# Stackduino-SMD.net
KiCad netlist of a schematic drawn in EAGLE
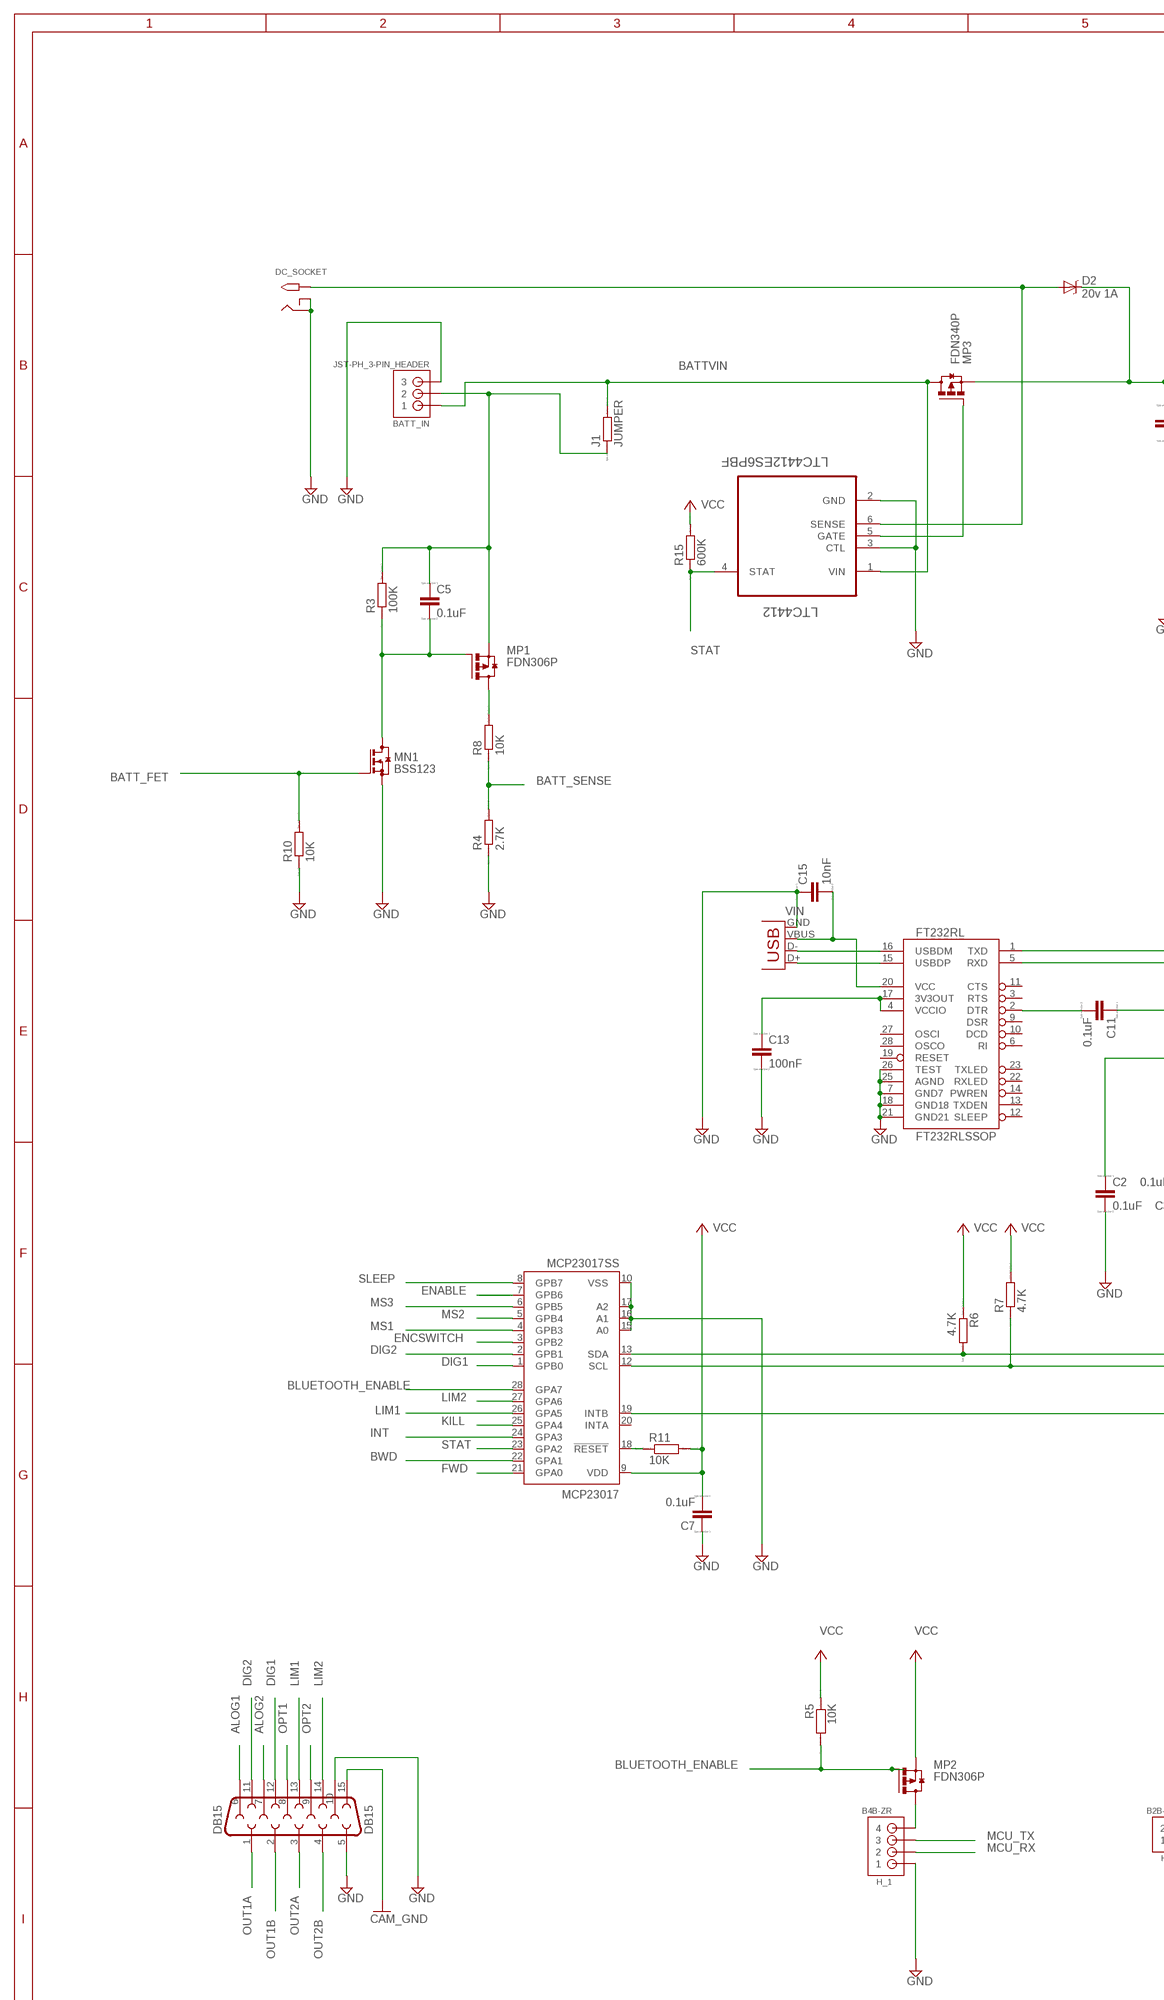
[diagram p0: schematic, sheet 1, part 1 of 2]
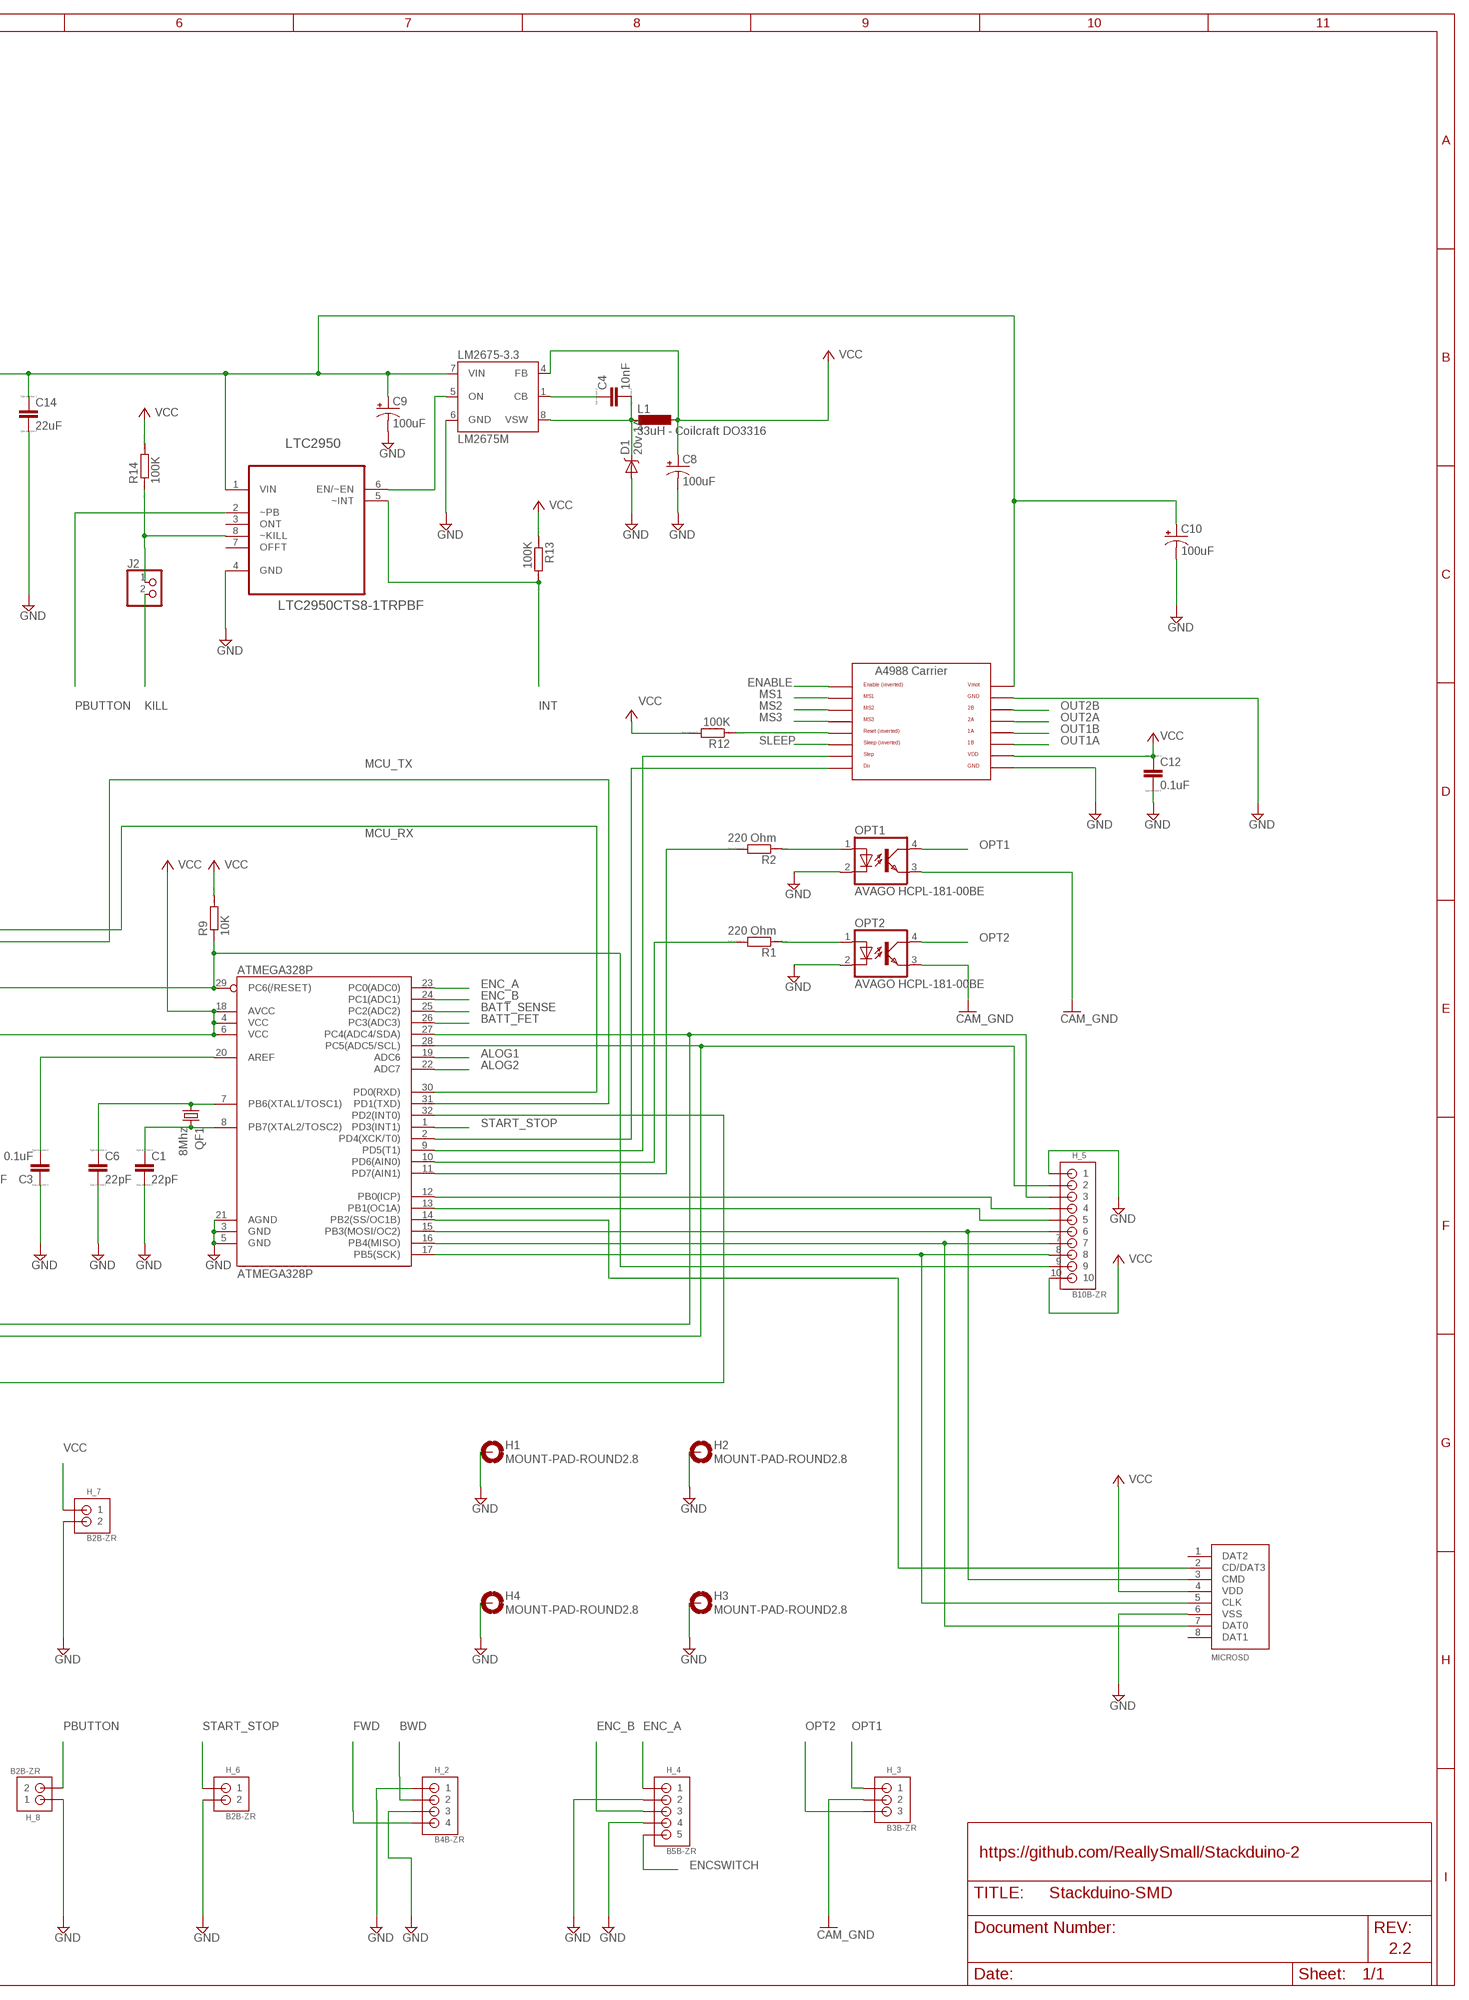
[diagram p1: schematic, sheet 1, part 2 of 2]

(export (version "E")
  (design (tool "Eeschema 10.0.6"))
  (components
    (comp (ref "A4988_CARRIER")
      (value "A4988BREAKOUT")
      (footprint "eagle-import:A4988BREAKOUT")
      (libsource (lib "eagle-import") (part "A4988BREAKOUT"))
    )
    (comp (ref "ATMEGA328P")
      (value "ATMEGA328P")
      (footprint "eagle-import:TQFP32-08")
      (libsource (lib "eagle-import") (part "ATMEGA328_SMT"))
    )
    (comp (ref "BATT_IN")
      (value "JST-PH_3-PIN_HEADER")
      (footprint "eagle-import:JST_B3B-PH_HEADER")
      (libsource (lib "eagle-import") (part "JST-PH_3-PIN_HEADER"))
    )
    (comp (ref "C1")
      (value "22pF")
      (footprint "eagle-import:C0805")
      (libsource (lib "eagle-import") (part "C"))
    )
    (comp (ref "C2")
      (value "0.1uF")
      (footprint "eagle-import:C0805")
      (libsource (lib "eagle-import") (part "C"))
    )
    (comp (ref "C3")
      (value "0.1uF")
      (footprint "eagle-import:C0805")
      (libsource (lib "eagle-import") (part "C"))
    )
    (comp (ref "C4")
      (value "10nF")
      (footprint "eagle-import:C0805")
      (libsource (lib "eagle-import") (part "C"))
    )
    (comp (ref "C5")
      (value "0.1uF")
      (footprint "eagle-import:C0805")
      (libsource (lib "eagle-import") (part "C"))
    )
    (comp (ref "C6")
      (value "22pF")
      (footprint "eagle-import:C0805")
      (libsource (lib "eagle-import") (part "C"))
    )
    (comp (ref "C7")
      (value "0.1uF")
      (footprint "eagle-import:C0805")
      (libsource (lib "eagle-import") (part "C"))
    )
    (comp (ref "C8")
      (value "100uF")
      (footprint "eagle-import:PANASONIC_D")
      (libsource (lib "eagle-import") (part "CAP_POLD"))
    )
    (comp (ref "C9")
      (value "100uF")
      (footprint "eagle-import:PANASONIC_D")
      (libsource (lib "eagle-import") (part "CAP_POLD"))
    )
    (comp (ref "C10")
      (value "100uF")
      (footprint "eagle-import:PANASONIC_D")
      (libsource (lib "eagle-import") (part "CAP_POLD"))
    )
    (comp (ref "C11")
      (value "0.1uF")
      (footprint "eagle-import:C0805")
      (libsource (lib "eagle-import") (part "C"))
    )
    (comp (ref "C12")
      (value "0.1uF")
      (footprint "eagle-import:C0805")
      (libsource (lib "eagle-import") (part "C"))
    )
    (comp (ref "C13")
      (value "100nF")
      (footprint "eagle-import:C0805")
      (libsource (lib "eagle-import") (part "C"))
    )
    (comp (ref "C14")
      (value "22uF")
      (footprint "eagle-import:C0805")
      (libsource (lib "eagle-import") (part "C"))
    )
    (comp (ref "C15")
      (value "10nF")
      (footprint "eagle-import:C0805")
      (libsource (lib "eagle-import") (part "C"))
    )
    (comp (ref "D1")
      (value "20v 1A")
      (footprint "eagle-import:SMA-DIODE")
      (libsource (lib "eagle-import") (part "MBRA140"))
    )
    (comp (ref "D2")
      (value "20v 1A")
      (footprint "eagle-import:SMA-DIODE")
      (libsource (lib "eagle-import") (part "MBRA140"))
    )
    (comp (ref "DB15")
      (value "DB15")
      (footprint "eagle-import:DB15")
      (libsource (lib "eagle-import") (part "DB15"))
    )
    (comp (ref "DC_SOCKET")
      (value "2.1MMJACKTHM")
      (footprint "eagle-import:PJ-102A")
      (libsource (lib "eagle-import") (part "2.1MMJACKTHM"))
    )
    (comp (ref "FT232RL")
      (value "FT232RLSSOP")
      (footprint "eagle-import:SSOP28DB")
      (libsource (lib "eagle-import") (part "FT232RLSSOP"))
    )
    (comp (ref "H1")
      (value "MOUNT-PAD-ROUND2.8")
      (footprint "eagle-import:2,8-PAD")
      (libsource (lib "eagle-import") (part "MOUNT-PAD-ROUND2.8"))
    )
    (comp (ref "H2")
      (value "MOUNT-PAD-ROUND2.8")
      (footprint "eagle-import:2,8-PAD")
      (libsource (lib "eagle-import") (part "MOUNT-PAD-ROUND2.8"))
    )
    (comp (ref "H3")
      (value "MOUNT-PAD-ROUND2.8")
      (footprint "eagle-import:2,8-PAD")
      (libsource (lib "eagle-import") (part "MOUNT-PAD-ROUND2.8"))
    )
    (comp (ref "H4")
      (value "MOUNT-PAD-ROUND2.8")
      (footprint "eagle-import:2,8-PAD")
      (libsource (lib "eagle-import") (part "MOUNT-PAD-ROUND2.8"))
    )
    (comp (ref "H_1")
      (value "B4B-ZR")
      (footprint "eagle-import:B4B-ZR")
      (libsource (lib "eagle-import") (part "B4B-ZR"))
    )
    (comp (ref "H_2")
      (value "B4B-ZR")
      (footprint "eagle-import:B4B-ZR")
      (libsource (lib "eagle-import") (part "B4B-ZR"))
    )
    (comp (ref "H_3")
      (value "B3B-ZR")
      (footprint "eagle-import:B3B-ZR")
      (libsource (lib "eagle-import") (part "B3B-ZR"))
    )
    (comp (ref "H_4")
      (value "B5B-ZR")
      (footprint "eagle-import:B5B-ZR")
      (libsource (lib "eagle-import") (part "B5B-ZR"))
    )
    (comp (ref "H_5")
      (value "B10B-ZR")
      (footprint "eagle-import:B10B-ZR")
      (libsource (lib "eagle-import") (part "B10B-ZR"))
    )
    (comp (ref "H_6")
      (value "B2B-ZR")
      (footprint "eagle-import:B2B-ZR")
      (libsource (lib "eagle-import") (part "B2B-ZR"))
    )
    (comp (ref "H_7")
      (value "B2B-ZR")
      (footprint "eagle-import:B2B-ZR")
      (libsource (lib "eagle-import") (part "B2B-ZR"))
    )
    (comp (ref "H_8")
      (value "B2B-ZR")
      (footprint "eagle-import:B2B-ZR")
      (libsource (lib "eagle-import") (part "B2B-ZR"))
    )
    (comp (ref "J1")
      (value "JUMPER")
      (footprint "eagle-import:R0805")
      (libsource (lib "eagle-import") (part "R"))
    )
    (comp (ref "J2")
      (value "PINHD-1X2")
      (footprint "eagle-import:1X02")
      (libsource (lib "eagle-import") (part "PINHD-1X2"))
    )
    (comp (ref "L1")
      (value "33uH - Coilcraft DO3316")
      (footprint "eagle-import:DO3316P")
      (libsource (lib "eagle-import") (part "DO3316P"))
    )
    (comp (ref "LM2675-3.3")
      (value "LM2675M")
      (footprint "eagle-import:SO08")
      (libsource (lib "eagle-import") (part "LM2675M"))
    )
    (comp (ref "LTC2950")
      (value "LTC2950CTS8-1TRPBF")
      (footprint "eagle-import:SOT65P280X100-8N")
      (fields (field (name "MPN") "LTC2950CTS8-1#TRPBF"))
      (libsource (lib "eagle-import") (part "LTC2950CTS8-1TRPBF"))
    )
    (comp (ref "LTC4412")
      (value "LTC4412ES6PBF")
      (footprint "eagle-import:SOT95P280X100-6N")
      (fields (field (name "MPN") "LTC4412ES6#PBF"))
      (libsource (lib "eagle-import") (part "LTC4412ES6PBF"))
    )
    (comp (ref "MCP23017")
      (value "MCP23017SS")
      (footprint "eagle-import:SSOP28")
      (libsource (lib "eagle-import") (part "MCP23017SS"))
    )
    (comp (ref "MICROSD")
      (value "CON_MICROSDHINGED")
      (footprint "eagle-import:CON_MICROSD_HINGED")
      (libsource (lib "eagle-import") (part "CON_MICROSDHINGED"))
    )
    (comp (ref "MN1")
      (value "BSS123")
      (footprint "eagle-import:SOT23")
      (libsource (lib "eagle-import") (part "BSS123"))
    )
    (comp (ref "MP1")
      (value "FDN306P")
      (footprint "eagle-import:SUPER-SOT3")
      (libsource (lib "eagle-import") (part "FDN360P"))
    )
    (comp (ref "MP2")
      (value "FDN306P")
      (footprint "eagle-import:SUPER-SOT3")
      (libsource (lib "eagle-import") (part "FDN360P"))
    )
    (comp (ref "MP3")
      (value "FDN340P")
      (footprint "eagle-import:SUPER-SOT3")
      (libsource (lib "eagle-import") (part "FDN360P"))
    )
    (comp (ref "OPT1")
      (value "AVAGO HCPL-181-00BE")
      (footprint "eagle-import:SMD4")
      (libsource (lib "eagle-import") (part "LTV816S"))
    )
    (comp (ref "OPT2")
      (value "AVAGO HCPL-181-00BE")
      (footprint "eagle-import:SMD4")
      (libsource (lib "eagle-import") (part "LTV816S"))
    )
    (comp (ref "QF1")
      (value "8Mhz")
      (footprint "eagle-import:HC49U-V")
      (libsource (lib "eagle-import") (part "CRYSTALHC49U-V"))
    )
    (comp (ref "R1")
      (value "220 Ohm")
      (footprint "eagle-import:R0805")
      (libsource (lib "eagle-import") (part "R"))
    )
    (comp (ref "R2")
      (value "220 Ohm")
      (footprint "eagle-import:R0805")
      (libsource (lib "eagle-import") (part "R"))
    )
    (comp (ref "R3")
      (value "100K")
      (footprint "eagle-import:R0805")
      (libsource (lib "eagle-import") (part "R"))
    )
    (comp (ref "R4")
      (value "2.7K")
      (footprint "eagle-import:R0805")
      (libsource (lib "eagle-import") (part "R"))
    )
    (comp (ref "R5")
      (value "10K")
      (footprint "eagle-import:R0805")
      (libsource (lib "eagle-import") (part "R"))
    )
    (comp (ref "R6")
      (value "4.7K")
      (footprint "eagle-import:R0805")
      (libsource (lib "eagle-import") (part "R"))
    )
    (comp (ref "R7")
      (value "4.7K")
      (footprint "eagle-import:R0805")
      (libsource (lib "eagle-import") (part "R"))
    )
    (comp (ref "R8")
      (value "10K")
      (footprint "eagle-import:R0805")
      (libsource (lib "eagle-import") (part "R"))
    )
    (comp (ref "R9")
      (value "10K")
      (footprint "eagle-import:R0805")
      (libsource (lib "eagle-import") (part "R"))
    )
    (comp (ref "R10")
      (value "10K")
      (footprint "eagle-import:R0805")
      (libsource (lib "eagle-import") (part "R"))
    )
    (comp (ref "R11")
      (value "10K")
      (footprint "eagle-import:R0805")
      (libsource (lib "eagle-import") (part "R"))
    )
    (comp (ref "R12")
      (value "100K")
      (footprint "eagle-import:R0805")
      (libsource (lib "eagle-import") (part "R"))
    )
    (comp (ref "R13")
      (value "100K")
      (footprint "eagle-import:R0805")
      (libsource (lib "eagle-import") (part "R"))
    )
    (comp (ref "R14")
      (value "100K")
      (footprint "eagle-import:R0805")
      (libsource (lib "eagle-import") (part "R"))
    )
    (comp (ref "R15")
      (value "600K")
      (footprint "eagle-import:R0805")
      (libsource (lib "eagle-import") (part "R"))
    )
    (comp (ref "USB")
      (value "USBSMD")
      (footprint "eagle-import:USB-MINIB")
      (libsource (lib "eagle-import") (part "USBSMD"))
    )
  )
  (nets
    (net (code "1") (name "/ALOG1") (class "Default")
      (node (ref "ATMEGA328P") (pin "19") (pinfunction "ADC6_19") (pintype "bidirectional"))
      (node (ref "DB15") (pin "6") (pinfunction "6_6") (pintype "passive"))
    )
    (net (code "2") (name "/ALOG2") (class "Default")
      (node (ref "ATMEGA328P") (pin "22") (pinfunction "ADC7_22") (pintype "bidirectional"))
      (node (ref "DB15") (pin "7") (pinfunction "7_7") (pintype "passive"))
    )
    (net (code "3") (name "/BATTVIN") (class "Default")
      (node (ref "BATT_IN") (pin "P1") (pinfunction "1_P1") (pintype "bidirectional"))
      (node (ref "J1") (pin "2") (pinfunction "2_2") (pintype "passive"))
      (node (ref "LTC4412") (pin "1") (pinfunction "VIN_1") (pintype "power_in"))
      (node (ref "MP3") (pin "3") (pinfunction "D_3") (pintype "passive"))
    )
    (net (code "4") (name "/BATT_FET") (class "Default")
      (node (ref "ATMEGA328P") (pin "26") (pinfunction "PC3(ADC3)_26") (pintype "bidirectional"))
      (node (ref "MN1") (pin "1") (pinfunction "G_1") (pintype "passive"))
      (node (ref "R10") (pin "2") (pinfunction "2_2") (pintype "passive"))
    )
    (net (code "5") (name "/BATT_SENSE") (class "Default")
      (node (ref "ATMEGA328P") (pin "25") (pinfunction "PC2(ADC2)_25") (pintype "bidirectional"))
      (node (ref "R4") (pin "2") (pinfunction "2_2") (pintype "passive"))
      (node (ref "R8") (pin "1") (pinfunction "1_1") (pintype "passive"))
    )
    (net (code "6") (name "/BLUETOOTH_ENABLE") (class "Default")
      (node (ref "MCP23017") (pin "28") (pinfunction "GPA7_28") (pintype "bidirectional"))
      (node (ref "MP2") (pin "1") (pinfunction "G_1") (pintype "passive"))
      (node (ref "R5") (pin "2") (pinfunction "2_2") (pintype "passive"))
    )
    (net (code "7") (name "/BWD") (class "Default")
      (node (ref "H_2") (pin "2") (pinfunction "2_2") (pintype "bidirectional"))
      (node (ref "MCP23017") (pin "22") (pinfunction "GPA1_22") (pintype "bidirectional"))
    )
    (net (code "8") (name "/DIG1") (class "Default")
      (node (ref "DB15") (pin "12") (pinfunction "12_12") (pintype "passive"))
      (node (ref "MCP23017") (pin "1") (pinfunction "GPB0_1") (pintype "bidirectional"))
    )
    (net (code "9") (name "/DIG2") (class "Default")
      (node (ref "DB15") (pin "11") (pinfunction "11_11") (pintype "passive"))
      (node (ref "MCP23017") (pin "2") (pinfunction "GPB1_2") (pintype "bidirectional"))
    )
    (net (code "10") (name "/ENABLE") (class "Default")
      (node (ref "A4988_CARRIER") (pin "EN") (pinfunction "EN_EN") (pintype "input"))
      (node (ref "MCP23017") (pin "7") (pinfunction "GPB6_7") (pintype "bidirectional"))
    )
    (net (code "11") (name "/ENCSWITCH") (class "Default")
      (node (ref "H_4") (pin "5") (pinfunction "5_5") (pintype "bidirectional"))
      (node (ref "MCP23017") (pin "3") (pinfunction "GPB2_3") (pintype "bidirectional"))
    )
    (net (code "12") (name "/ENC_A") (class "Default")
      (node (ref "ATMEGA328P") (pin "23") (pinfunction "PC0(ADC0)_23") (pintype "bidirectional"))
      (node (ref "H_4") (pin "1") (pinfunction "1_1") (pintype "bidirectional"))
    )
    (net (code "13") (name "/ENC_B") (class "Default")
      (node (ref "ATMEGA328P") (pin "24") (pinfunction "PC1(ADC1)_24") (pintype "bidirectional"))
      (node (ref "H_4") (pin "3") (pinfunction "3_3") (pintype "bidirectional"))
    )
    (net (code "14") (name "/FWD") (class "Default")
      (node (ref "H_2") (pin "4") (pinfunction "4_4") (pintype "bidirectional"))
      (node (ref "MCP23017") (pin "21") (pinfunction "GPA0_21") (pintype "bidirectional"))
    )
    (net (code "15") (name "/INT") (class "Default")
      (node (ref "LTC2950") (pin "5") (pinfunction "~{INT}_5") (pintype "output"))
      (node (ref "MCP23017") (pin "24") (pinfunction "GPA3_24") (pintype "bidirectional"))
      (node (ref "R13") (pin "2") (pinfunction "2_2") (pintype "passive"))
    )
    (net (code "16") (name "/KILL") (class "Default")
      (node (ref "J2") (pin "2") (pinfunction "2_2") (pintype "passive"))
      (node (ref "MCP23017") (pin "25") (pinfunction "GPA4_25") (pintype "bidirectional"))
    )
    (net (code "17") (name "/LIM1") (class "Default")
      (node (ref "DB15") (pin "13") (pinfunction "13_13") (pintype "passive"))
      (node (ref "MCP23017") (pin "26") (pinfunction "GPA5_26") (pintype "bidirectional"))
    )
    (net (code "18") (name "/LIM2") (class "Default")
      (node (ref "DB15") (pin "14") (pinfunction "14_14") (pintype "passive"))
      (node (ref "MCP23017") (pin "27") (pinfunction "GPA6_27") (pintype "bidirectional"))
    )
    (net (code "19") (name "/MCU_RX") (class "Default")
      (node (ref "ATMEGA328P") (pin "30") (pinfunction "PD0(RXD)_30") (pintype "bidirectional"))
      (node (ref "FT232RL") (pin "1") (pinfunction "TXD_1") (pintype "output"))
      (node (ref "H_1") (pin "2") (pinfunction "2_2") (pintype "bidirectional"))
    )
    (net (code "20") (name "/MCU_TX") (class "Default")
      (node (ref "ATMEGA328P") (pin "31") (pinfunction "PD1(TXD)_31") (pintype "bidirectional"))
      (node (ref "FT232RL") (pin "5") (pinfunction "RXD_5") (pintype "input"))
      (node (ref "H_1") (pin "3") (pinfunction "3_3") (pintype "bidirectional"))
    )
    (net (code "21") (name "/MS1") (class "Default")
      (node (ref "A4988_CARRIER") (pin "MS1") (pinfunction "MS1_MS1") (pintype "input"))
      (node (ref "MCP23017") (pin "4") (pinfunction "GPB3_4") (pintype "bidirectional"))
    )
    (net (code "22") (name "/MS2") (class "Default")
      (node (ref "A4988_CARRIER") (pin "MS2") (pinfunction "MS2_MS2") (pintype "input"))
      (node (ref "MCP23017") (pin "5") (pinfunction "GPB4_5") (pintype "bidirectional"))
    )
    (net (code "23") (name "/MS3") (class "Default")
      (node (ref "A4988_CARRIER") (pin "MS3") (pinfunction "MS3_MS3") (pintype "input"))
      (node (ref "MCP23017") (pin "6") (pinfunction "GPB5_6") (pintype "bidirectional"))
    )
    (net (code "24") (name "/OPT1") (class "Default")
      (node (ref "DB15") (pin "8") (pinfunction "8_8") (pintype "passive"))
      (node (ref "H_3") (pin "1") (pinfunction "1_1") (pintype "bidirectional"))
      (node (ref "OPT1") (pin "4") (pinfunction "COL_4") (pintype "passive"))
    )
    (net (code "25") (name "/OPT2") (class "Default")
      (node (ref "DB15") (pin "9") (pinfunction "9_9") (pintype "passive"))
      (node (ref "H_3") (pin "3") (pinfunction "3_3") (pintype "bidirectional"))
      (node (ref "OPT2") (pin "4") (pinfunction "COL_4") (pintype "passive"))
    )
    (net (code "26") (name "/OUT1A") (class "Default")
      (node (ref "A4988_CARRIER") (pin "1B") (pinfunction "1B_1B") (pintype "output"))
      (node (ref "DB15") (pin "1") (pinfunction "1_1") (pintype "passive"))
    )
    (net (code "27") (name "/OUT1B") (class "Default")
      (node (ref "A4988_CARRIER") (pin "1A") (pinfunction "1A_1A") (pintype "output"))
      (node (ref "DB15") (pin "2") (pinfunction "2_2") (pintype "passive"))
    )
    (net (code "28") (name "/OUT2A") (class "Default")
      (node (ref "A4988_CARRIER") (pin "2A") (pinfunction "2A_2A") (pintype "output"))
      (node (ref "DB15") (pin "3") (pinfunction "3_3") (pintype "passive"))
    )
    (net (code "29") (name "/OUT2B") (class "Default")
      (node (ref "A4988_CARRIER") (pin "2B") (pinfunction "2B_2B") (pintype "output"))
      (node (ref "DB15") (pin "4") (pinfunction "4_4") (pintype "passive"))
    )
    (net (code "30") (name "/PBUTTON") (class "Default")
      (node (ref "H_8") (pin "2") (pinfunction "2_2") (pintype "bidirectional"))
      (node (ref "LTC2950") (pin "2") (pinfunction "~{PB}_2") (pintype "input"))
    )
    (net (code "31") (name "/SLEEP") (class "Default")
      (node (ref "A4988_CARRIER") (pin "SLP") (pinfunction "SLEEP_SLP") (pintype "input"))
      (node (ref "MCP23017") (pin "8") (pinfunction "GPB7_8") (pintype "bidirectional"))
    )
    (net (code "32") (name "/START_STOP") (class "Default")
      (node (ref "ATMEGA328P") (pin "1") (pinfunction "PD3(INT1)_1") (pintype "bidirectional"))
      (node (ref "H_6") (pin "1") (pinfunction "1_1") (pintype "bidirectional"))
    )
    (net (code "33") (name "/STAT") (class "Default")
      (node (ref "LTC4412") (pin "4") (pinfunction "STAT_4") (pintype "output"))
      (node (ref "MCP23017") (pin "23") (pinfunction "GPA2_23") (pintype "bidirectional"))
      (node (ref "R15") (pin "1") (pinfunction "1_1") (pintype "passive"))
    )
    (net (code "34") (name "/VIN") (class "Default")
      (node (ref "D2") (pin "A") (pinfunction "A_A") (pintype "passive"))
      (node (ref "DC_SOCKET") (pin "TIP") (pinfunction "TIP_TIP") (pintype "bidirectional"))
      (node (ref "LTC4412") (pin "6") (pinfunction "SENSE_6") (pintype "input"))
    )
    (net (code "35") (name "CAM_GND") (class "Default")
      (node (ref "DB15") (pin "15") (pinfunction "15_15") (pintype "passive"))
      (node (ref "H_3") (pin "2") (pinfunction "2_2") (pintype "bidirectional"))
      (node (ref "OPT1") (pin "3") (pinfunction "EMIT_3") (pintype "passive"))
      (node (ref "OPT2") (pin "3") (pinfunction "EMIT_3") (pintype "passive"))
    )
    (net (code "36") (name "GND") (class "Default")
      (node (ref "A4988_CARRIER") (pin "GND") (pinfunction "GND_GND") (pintype "power_in"))
      (node (ref "A4988_CARRIER") (pin "GND@0") (pinfunction "GND_GND@0") (pintype "power_in"))
      (node (ref "ATMEGA328P") (pin "21") (pinfunction "AGND_21") (pintype "bidirectional"))
      (node (ref "ATMEGA328P") (pin "3") (pinfunction "GND_3") (pintype "bidirectional"))
      (node (ref "ATMEGA328P") (pin "5") (pinfunction "GND_5") (pintype "bidirectional"))
      (node (ref "BATT_IN") (pin "P3") (pinfunction "3_P3") (pintype "bidirectional"))
      (node (ref "C1") (pin "2") (pinfunction "2_2") (pintype "passive"))
      (node (ref "C10") (pin "-") (pinfunction "-_-") (pintype "passive"))
      (node (ref "C12") (pin "2") (pinfunction "2_2") (pintype "passive"))
      (node (ref "C13") (pin "2") (pinfunction "2_2") (pintype "passive"))
      (node (ref "C14") (pin "2") (pinfunction "2_2") (pintype "passive"))
      (node (ref "C15") (pin "1") (pinfunction "1_1") (pintype "passive"))
      (node (ref "C2") (pin "2") (pinfunction "2_2") (pintype "passive"))
      (node (ref "C3") (pin "1") (pinfunction "1_1") (pintype "passive"))
      (node (ref "C6") (pin "2") (pinfunction "2_2") (pintype "passive"))
      (node (ref "C7") (pin "1") (pinfunction "1_1") (pintype "passive"))
      (node (ref "C8") (pin "-") (pinfunction "-_-") (pintype "passive"))
      (node (ref "C9") (pin "-") (pinfunction "-_-") (pintype "passive"))
      (node (ref "D1") (pin "A") (pinfunction "A_A") (pintype "passive"))
      (node (ref "DB15") (pin "10") (pinfunction "10_10") (pintype "passive"))
      (node (ref "DB15") (pin "5") (pinfunction "5_5") (pintype "passive"))
      (node (ref "DC_SOCKET") (pin "RING") (pinfunction "RING_RING") (pintype "bidirectional"))
      (node (ref "DC_SOCKET") (pin "RING_SW") (pinfunction "RING_SW_RING_SW") (pintype "bidirectional"))
      (node (ref "FT232RL") (pin "18") (pinfunction "GND18_18") (pintype "power_in"))
      (node (ref "FT232RL") (pin "21") (pinfunction "GND21_21") (pintype "power_in"))
      (node (ref "FT232RL") (pin "25") (pinfunction "AGND_25") (pintype "power_in"))
      (node (ref "FT232RL") (pin "26") (pinfunction "TEST_26") (pintype "input"))
      (node (ref "FT232RL") (pin "7") (pinfunction "GND7_7") (pintype "power_in"))
      (node (ref "H1") (pin "B2,8") (pinfunction "MOUNT_B2,8") (pintype "passive"))
      (node (ref "H2") (pin "B2,8") (pinfunction "MOUNT_B2,8") (pintype "passive"))
      (node (ref "H3") (pin "B2,8") (pinfunction "MOUNT_B2,8") (pintype "passive"))
      (node (ref "H4") (pin "B2,8") (pinfunction "MOUNT_B2,8") (pintype "passive"))
      (node (ref "H_1") (pin "1") (pinfunction "1_1") (pintype "bidirectional"))
      (node (ref "H_2") (pin "1") (pinfunction "1_1") (pintype "bidirectional"))
      (node (ref "H_2") (pin "3") (pinfunction "3_3") (pintype "bidirectional"))
      (node (ref "H_4") (pin "2") (pinfunction "2_2") (pintype "bidirectional"))
      (node (ref "H_4") (pin "4") (pinfunction "4_4") (pintype "bidirectional"))
      (node (ref "H_5") (pin "1") (pinfunction "1_1") (pintype "bidirectional"))
      (node (ref "H_6") (pin "2") (pinfunction "2_2") (pintype "bidirectional"))
      (node (ref "H_7") (pin "2") (pinfunction "2_2") (pintype "bidirectional"))
      (node (ref "H_8") (pin "1") (pinfunction "1_1") (pintype "bidirectional"))
      (node (ref "LM2675-3.3") (pin "6") (pinfunction "GND_6") (pintype "power_in"))
      (node (ref "LTC2950") (pin "4") (pinfunction "GND_4") (pintype "passive"))
      (node (ref "LTC4412") (pin "2") (pinfunction "GND_2") (pintype "passive"))
      (node (ref "LTC4412") (pin "3") (pinfunction "CTL_3") (pintype "input"))
      (node (ref "MCP23017") (pin "10") (pinfunction "VSS_10") (pintype "power_in"))
      (node (ref "MCP23017") (pin "15") (pinfunction "A0_15") (pintype "input"))
      (node (ref "MCP23017") (pin "16") (pinfunction "A1_16") (pintype "input"))
      (node (ref "MCP23017") (pin "17") (pinfunction "A2_17") (pintype "input"))
      (node (ref "MICROSD") (pin "6") (pinfunction "VSS_6") (pintype "bidirectional"))
      (node (ref "MN1") (pin "2") (pinfunction "S_2") (pintype "passive"))
      (node (ref "OPT1") (pin "2") (pinfunction "C_2") (pintype "passive"))
      (node (ref "OPT2") (pin "2") (pinfunction "C_2") (pintype "passive"))
      (node (ref "R10") (pin "1") (pinfunction "1_1") (pintype "passive"))
      (node (ref "R4") (pin "1") (pinfunction "1_1") (pintype "passive"))
      (node (ref "USB") (pin "GND") (pinfunction "GND_GND") (pintype "bidirectional"))
    )
    (net (code "37") (name "Net-(A4988_CARRIER-PadRST)") (class "Default")
      (node (ref "A4988_CARRIER") (pin "RST") (pinfunction "RST_RST") (pintype "input"))
      (node (ref "R12") (pin "1") (pinfunction "1_1") (pintype "passive"))
    )
    (net (code "38") (name "Net-(ATMEGA328P-AREF)") (class "Default")
      (node (ref "ATMEGA328P") (pin "20") (pinfunction "AREF_20") (pintype "bidirectional"))
      (node (ref "C3") (pin "2") (pinfunction "2_2") (pintype "passive"))
    )
    (net (code "39") (name "Net-(ATMEGA328P-PB0(ICP))") (class "Default")
      (node (ref "ATMEGA328P") (pin "12") (pinfunction "PB0(ICP)_12") (pintype "bidirectional"))
      (node (ref "H_5") (pin "4") (pinfunction "4_4") (pintype "bidirectional"))
    )
    (net (code "40") (name "Net-(ATMEGA328P-PB1(OC1A))") (class "Default")
      (node (ref "ATMEGA328P") (pin "13") (pinfunction "PB1(OC1A)_13") (pintype "bidirectional"))
      (node (ref "H_5") (pin "5") (pinfunction "5_5") (pintype "bidirectional"))
    )
    (net (code "41") (name "Net-(ATMEGA328P-PB2(SS{slash}OC1B))") (class "Default")
      (node (ref "ATMEGA328P") (pin "14") (pinfunction "PB2(SS/OC1B)_14") (pintype "bidirectional"))
      (node (ref "MICROSD") (pin "2") (pinfunction "CD/DAT3_2") (pintype "bidirectional"))
    )
    (net (code "42") (name "Net-(ATMEGA328P-PB3(MOSI{slash}OC2))") (class "Default")
      (node (ref "ATMEGA328P") (pin "15") (pinfunction "PB3(MOSI/OC2)_15") (pintype "bidirectional"))
      (node (ref "H_5") (pin "6") (pinfunction "6_6") (pintype "bidirectional"))
      (node (ref "MICROSD") (pin "3") (pinfunction "CMD_3") (pintype "bidirectional"))
    )
    (net (code "43") (name "Net-(ATMEGA328P-PB4(MISO))") (class "Default")
      (node (ref "ATMEGA328P") (pin "16") (pinfunction "PB4(MISO)_16") (pintype "bidirectional"))
      (node (ref "H_5") (pin "7") (pinfunction "7_7") (pintype "bidirectional"))
      (node (ref "MICROSD") (pin "7") (pinfunction "DAT0_7") (pintype "bidirectional"))
    )
    (net (code "44") (name "Net-(ATMEGA328P-PB5(SCK))") (class "Default")
      (node (ref "ATMEGA328P") (pin "17") (pinfunction "PB5(SCK)_17") (pintype "bidirectional"))
      (node (ref "H_5") (pin "8") (pinfunction "8_8") (pintype "bidirectional"))
      (node (ref "MICROSD") (pin "5") (pinfunction "CLK_5") (pintype "bidirectional"))
    )
    (net (code "45") (name "Net-(ATMEGA328P-PB6(XTAL1{slash}TOSC1))") (class "Default")
      (node (ref "ATMEGA328P") (pin "7") (pinfunction "PB6(XTAL1/TOSC1)_7") (pintype "bidirectional"))
      (node (ref "C6") (pin "1") (pinfunction "1_1") (pintype "passive"))
      (node (ref "QF1") (pin "1") (pinfunction "1_1") (pintype "passive"))
    )
    (net (code "46") (name "Net-(ATMEGA328P-PB7(XTAL2{slash}TOSC2))") (class "Default")
      (node (ref "ATMEGA328P") (pin "8") (pinfunction "PB7(XTAL2/TOSC2)_8") (pintype "bidirectional"))
      (node (ref "C1") (pin "1") (pinfunction "1_1") (pintype "passive"))
      (node (ref "QF1") (pin "2") (pinfunction "2_2") (pintype "passive"))
    )
    (net (code "47") (name "Net-(ATMEGA328P-PC4(ADC4{slash}SDA))") (class "Default")
      (node (ref "ATMEGA328P") (pin "27") (pinfunction "PC4(ADC4/SDA)_27") (pintype "bidirectional"))
      (node (ref "H_5") (pin "3") (pinfunction "3_3") (pintype "bidirectional"))
      (node (ref "MCP23017") (pin "13") (pinfunction "SDA_13") (pintype "bidirectional"))
      (node (ref "R6") (pin "2") (pinfunction "2_2") (pintype "passive"))
    )
    (net (code "48") (name "Net-(ATMEGA328P-PC5(ADC5{slash}SCL))") (class "Default")
      (node (ref "ATMEGA328P") (pin "28") (pinfunction "PC5(ADC5/SCL)_28") (pintype "bidirectional"))
      (node (ref "H_5") (pin "2") (pinfunction "2_2") (pintype "bidirectional"))
      (node (ref "MCP23017") (pin "12") (pinfunction "SCL_12") (pintype "input"))
      (node (ref "R7") (pin "1") (pinfunction "1_1") (pintype "passive"))
    )
    (net (code "49") (name "Net-(ATMEGA328P-PC6({slash}RESET))") (class "Default")
      (node (ref "ATMEGA328P") (pin "29") (pinfunction "PC6(/RESET)_29") (pintype "bidirectional"))
      (node (ref "C11") (pin "1") (pinfunction "1_1") (pintype "passive"))
      (node (ref "H_5") (pin "9") (pinfunction "9_9") (pintype "bidirectional"))
      (node (ref "R9") (pin "1") (pinfunction "1_1") (pintype "passive"))
    )
    (net (code "50") (name "Net-(ATMEGA328P-PD2(INT0))") (class "Default")
      (node (ref "ATMEGA328P") (pin "32") (pinfunction "PD2(INT0)_32") (pintype "bidirectional"))
      (node (ref "MCP23017") (pin "19") (pinfunction "INTB_19") (pintype "output"))
    )
    (net (code "51") (name "Net-(ATMEGA328P-PD4(XCK{slash}T0))") (class "Default")
      (node (ref "A4988_CARRIER") (pin "DIR") (pinfunction "DIR_DIR") (pintype "input"))
      (node (ref "ATMEGA328P") (pin "2") (pinfunction "PD4(XCK/T0)_2") (pintype "bidirectional"))
    )
    (net (code "52") (name "Net-(ATMEGA328P-PD5(T1))") (class "Default")
      (node (ref "A4988_CARRIER") (pin "STEP") (pinfunction "STEP_STEP") (pintype "input"))
      (node (ref "ATMEGA328P") (pin "9") (pinfunction "PD5(T1)_9") (pintype "bidirectional"))
    )
    (net (code "53") (name "Net-(ATMEGA328P-PD6(AIN0))") (class "Default")
      (node (ref "ATMEGA328P") (pin "10") (pinfunction "PD6(AIN0)_10") (pintype "bidirectional"))
      (node (ref "R1") (pin "2") (pinfunction "2_2") (pintype "passive"))
    )
    (net (code "54") (name "Net-(ATMEGA328P-PD7(AIN1))") (class "Default")
      (node (ref "ATMEGA328P") (pin "11") (pinfunction "PD7(AIN1)_11") (pintype "bidirectional"))
      (node (ref "R2") (pin "2") (pinfunction "2_2") (pintype "passive"))
    )
    (net (code "55") (name "Net-(BATT_IN-2)") (class "Default")
      (node (ref "BATT_IN") (pin "P2") (pinfunction "2_P2") (pintype "bidirectional"))
      (node (ref "C5") (pin "1") (pinfunction "1_1") (pintype "passive"))
      (node (ref "J1") (pin "1") (pinfunction "1_1") (pintype "passive"))
      (node (ref "MP1") (pin "2") (pinfunction "S_2") (pintype "passive"))
      (node (ref "R3") (pin "2") (pinfunction "2_2") (pintype "passive"))
    )
    (net (code "56") (name "Net-(FT232RL-3V3OUT)") (class "Default")
      (node (ref "C13") (pin "1") (pinfunction "1_1") (pintype "passive"))
      (node (ref "FT232RL") (pin "17") (pinfunction "3V3OUT_17") (pintype "output"))
      (node (ref "FT232RL") (pin "4") (pinfunction "VCCIO_4") (pintype "power_in"))
    )
    (net (code "57") (name "Net-(FT232RL-DTR)") (class "Default")
      (node (ref "C11") (pin "2") (pinfunction "2_2") (pintype "passive"))
      (node (ref "FT232RL") (pin "2") (pinfunction "DTR_2") (pintype "output"))
    )
    (net (code "58") (name "Net-(FT232RL-USBDM)") (class "Default")
      (node (ref "FT232RL") (pin "16") (pinfunction "USBDM_16") (pintype "bidirectional"))
      (node (ref "USB") (pin "D-") (pinfunction "D-_D-") (pintype "bidirectional"))
    )
    (net (code "59") (name "Net-(FT232RL-USBDP)") (class "Default")
      (node (ref "FT232RL") (pin "15") (pinfunction "USBDP_15") (pintype "bidirectional"))
      (node (ref "USB") (pin "D+") (pinfunction "D+_D+") (pintype "bidirectional"))
    )
    (net (code "60") (name "Net-(FT232RL-VCC)") (class "Default")
      (node (ref "C15") (pin "2") (pinfunction "2_2") (pintype "passive"))
      (node (ref "FT232RL") (pin "20") (pinfunction "VCC_20") (pintype "power_in"))
      (node (ref "USB") (pin "VBUS") (pinfunction "VBUS_VBUS") (pintype "bidirectional"))
    )
    (net (code "61") (name "Net-(LM2675-3.3-CB)") (class "Default")
      (node (ref "C4") (pin "1") (pinfunction "1_1") (pintype "passive"))
      (node (ref "LM2675-3.3") (pin "1") (pinfunction "CB_1") (pintype "input"))
    )
    (net (code "62") (name "Net-(LM2675-3.3-ON)") (class "Default")
      (node (ref "LM2675-3.3") (pin "5") (pinfunction "ON_5") (pintype "passive"))
      (node (ref "LTC2950") (pin "6") (pinfunction "EN/~{EN}_6") (pintype "output"))
    )
    (net (code "63") (name "Net-(LM2675-3.3-VIN)") (class "Default")
      (node (ref "A4988_CARRIER") (pin "VMOT") (pinfunction "VMOT_VMOT") (pintype "power_in"))
      (node (ref "C10") (pin "+") (pinfunction "+_+") (pintype "passive"))
      (node (ref "C14") (pin "1") (pinfunction "1_1") (pintype "passive"))
      (node (ref "C9") (pin "+") (pinfunction "+_+") (pintype "passive"))
      (node (ref "D2") (pin "C") (pinfunction "C_C") (pintype "passive"))
      (node (ref "LM2675-3.3") (pin "7") (pinfunction "VIN_7") (pintype "power_in"))
      (node (ref "LTC2950") (pin "1") (pinfunction "VIN_1") (pintype "power_in"))
      (node (ref "MP3") (pin "2") (pinfunction "S_2") (pintype "passive"))
    )
    (net (code "64") (name "Net-(LM2675-3.3-VSW)") (class "Default")
      (node (ref "C4") (pin "2") (pinfunction "2_2") (pintype "passive"))
      (node (ref "D1") (pin "C") (pinfunction "C_C") (pintype "passive"))
      (node (ref "L1") (pin "1") (pinfunction "1_1") (pintype "passive"))
      (node (ref "LM2675-3.3") (pin "8") (pinfunction "VSW_8") (pintype "output"))
    )
    (net (code "65") (name "Net-(LTC2950-~{KILL})") (class "Default")
      (node (ref "J2") (pin "1") (pinfunction "1_1") (pintype "passive"))
      (node (ref "LTC2950") (pin "8") (pinfunction "~{KILL}_8") (pintype "input"))
      (node (ref "R14") (pin "1") (pinfunction "1_1") (pintype "passive"))
    )
    (net (code "66") (name "Net-(LTC4412-GATE)") (class "Default")
      (node (ref "LTC4412") (pin "5") (pinfunction "GATE_5") (pintype "input"))
      (node (ref "MP3") (pin "1") (pinfunction "G_1") (pintype "passive"))
    )
    (net (code "67") (name "Net-(MCP23017-~{RESET})") (class "Default")
      (node (ref "MCP23017") (pin "18") (pinfunction "~{RESET}_18") (pintype "input"))
      (node (ref "R11") (pin "1") (pinfunction "1_1") (pintype "passive"))
    )
    (net (code "68") (name "Net-(MN1-D)") (class "Default")
      (node (ref "C5") (pin "2") (pinfunction "2_2") (pintype "passive"))
      (node (ref "MN1") (pin "3") (pinfunction "D_3") (pintype "passive"))
      (node (ref "MP1") (pin "1") (pinfunction "G_1") (pintype "passive"))
      (node (ref "R3") (pin "1") (pinfunction "1_1") (pintype "passive"))
    )
    (net (code "69") (name "Net-(MP1-D)") (class "Default")
      (node (ref "MP1") (pin "3") (pinfunction "D_3") (pintype "passive"))
      (node (ref "R8") (pin "2") (pinfunction "2_2") (pintype "passive"))
    )
    (net (code "70") (name "Net-(MP2-D)") (class "Default")
      (node (ref "H_1") (pin "4") (pinfunction "4_4") (pintype "bidirectional"))
      (node (ref "MP2") (pin "3") (pinfunction "D_3") (pintype "passive"))
    )
    (net (code "71") (name "Net-(OPT1-A)") (class "Default")
      (node (ref "OPT1") (pin "1") (pinfunction "A_1") (pintype "passive"))
      (node (ref "R2") (pin "1") (pinfunction "1_1") (pintype "passive"))
    )
    (net (code "72") (name "Net-(OPT2-A)") (class "Default")
      (node (ref "OPT2") (pin "1") (pinfunction "A_1") (pintype "passive"))
      (node (ref "R1") (pin "1") (pinfunction "1_1") (pintype "passive"))
    )
    (net (code "73") (name "VCC") (class "Default")
      (node (ref "A4988_CARRIER") (pin "VDD") (pinfunction "VDD_VDD") (pintype "power_in"))
      (node (ref "ATMEGA328P") (pin "18") (pinfunction "AVCC_18") (pintype "bidirectional"))
      (node (ref "ATMEGA328P") (pin "4") (pinfunction "VCC_4") (pintype "bidirectional"))
      (node (ref "ATMEGA328P") (pin "6") (pinfunction "VCC_6") (pintype "bidirectional"))
      (node (ref "C12") (pin "1") (pinfunction "1_1") (pintype "passive"))
      (node (ref "C2") (pin "1") (pinfunction "1_1") (pintype "passive"))
      (node (ref "C7") (pin "2") (pinfunction "2_2") (pintype "passive"))
      (node (ref "C8") (pin "+") (pinfunction "+_+") (pintype "passive"))
      (node (ref "H_5") (pin "10") (pinfunction "10_10") (pintype "bidirectional"))
      (node (ref "H_7") (pin "1") (pinfunction "1_1") (pintype "bidirectional"))
      (node (ref "L1") (pin "2") (pinfunction "2_2") (pintype "passive"))
      (node (ref "LM2675-3.3") (pin "4") (pinfunction "FB_4") (pintype "input"))
      (node (ref "MCP23017") (pin "9") (pinfunction "VDD_9") (pintype "power_in"))
      (node (ref "MICROSD") (pin "4") (pinfunction "VDD_4") (pintype "bidirectional"))
      (node (ref "MP2") (pin "2") (pinfunction "S_2") (pintype "passive"))
      (node (ref "R11") (pin "2") (pinfunction "2_2") (pintype "passive"))
      (node (ref "R12") (pin "2") (pinfunction "2_2") (pintype "passive"))
      (node (ref "R13") (pin "1") (pinfunction "1_1") (pintype "passive"))
      (node (ref "R14") (pin "2") (pinfunction "2_2") (pintype "passive"))
      (node (ref "R15") (pin "2") (pinfunction "2_2") (pintype "passive"))
      (node (ref "R5") (pin "1") (pinfunction "1_1") (pintype "passive"))
      (node (ref "R6") (pin "1") (pinfunction "1_1") (pintype "passive"))
      (node (ref "R7") (pin "2") (pinfunction "2_2") (pintype "passive"))
      (node (ref "R9") (pin "2") (pinfunction "2_2") (pintype "passive"))
    )
    (net (code "74") (name "unconnected-(FT232RL-CTS-Pad11)") (class "Default")
      (node (ref "FT232RL") (pin "11") (pinfunction "CTS_11") (pintype "input"))
    )
    (net (code "75") (name "unconnected-(FT232RL-DCD-Pad10)") (class "Default")
      (node (ref "FT232RL") (pin "10") (pinfunction "DCD_10") (pintype "input"))
    )
    (net (code "76") (name "unconnected-(FT232RL-DSR-Pad9)") (class "Default")
      (node (ref "FT232RL") (pin "9") (pinfunction "DSR_9") (pintype "input"))
    )
    (net (code "77") (name "unconnected-(FT232RL-OSCI-Pad27)") (class "Default")
      (node (ref "FT232RL") (pin "27") (pinfunction "OSCI_27") (pintype "input"))
    )
    (net (code "78") (name "unconnected-(FT232RL-OSCO-Pad28)") (class "Default")
      (node (ref "FT232RL") (pin "28") (pinfunction "OSCO_28") (pintype "output"))
    )
    (net (code "79") (name "unconnected-(FT232RL-PWREN-Pad14)") (class "Default")
      (node (ref "FT232RL") (pin "14") (pinfunction "PWREN_14") (pintype "input"))
    )
    (net (code "80") (name "unconnected-(FT232RL-RESET-Pad19)") (class "Default")
      (node (ref "FT232RL") (pin "19") (pinfunction "RESET_19") (pintype "input"))
    )
    (net (code "81") (name "unconnected-(FT232RL-RI-Pad6)") (class "Default")
      (node (ref "FT232RL") (pin "6") (pinfunction "RI_6") (pintype "input"))
    )
    (net (code "82") (name "unconnected-(FT232RL-RTS-Pad3)") (class "Default")
      (node (ref "FT232RL") (pin "3") (pinfunction "RTS_3") (pintype "output"))
    )
    (net (code "83") (name "unconnected-(FT232RL-RXLED-Pad22)") (class "Default")
      (node (ref "FT232RL") (pin "22") (pinfunction "RXLED_22") (pintype "input"))
    )
    (net (code "84") (name "unconnected-(FT232RL-SLEEP-Pad12)") (class "Default")
      (node (ref "FT232RL") (pin "12") (pinfunction "SLEEP_12") (pintype "input"))
    )
    (net (code "85") (name "unconnected-(FT232RL-TXDEN-Pad13)") (class "Default")
      (node (ref "FT232RL") (pin "13") (pinfunction "TXDEN_13") (pintype "input"))
    )
    (net (code "86") (name "unconnected-(FT232RL-TXLED-Pad23)") (class "Default")
      (node (ref "FT232RL") (pin "23") (pinfunction "TXLED_23") (pintype "input"))
    )
    (net (code "87") (name "unconnected-(LTC2950-OFFT-Pad7)") (class "Default")
      (node (ref "LTC2950") (pin "7") (pinfunction "OFFT_7") (pintype "input"))
    )
    (net (code "88") (name "unconnected-(LTC2950-ONT-Pad3)") (class "Default")
      (node (ref "LTC2950") (pin "3") (pinfunction "ONT_3") (pintype "input"))
    )
    (net (code "89") (name "unconnected-(MCP23017-INTA-Pad20)") (class "Default")
      (node (ref "MCP23017") (pin "20") (pinfunction "INTA_20") (pintype "output"))
    )
    (net (code "90") (name "unconnected-(MICROSD-DAT1-Pad8)") (class "Default")
      (node (ref "MICROSD") (pin "8") (pinfunction "DAT1_8") (pintype "bidirectional"))
    )
    (net (code "91") (name "unconnected-(MICROSD-DAT2-Pad1)") (class "Default")
      (node (ref "MICROSD") (pin "1") (pinfunction "DAT2_1") (pintype "bidirectional"))
    )
  )
)
